# ai.net
KiCad netlist of a schematic drawn in Altium Designer
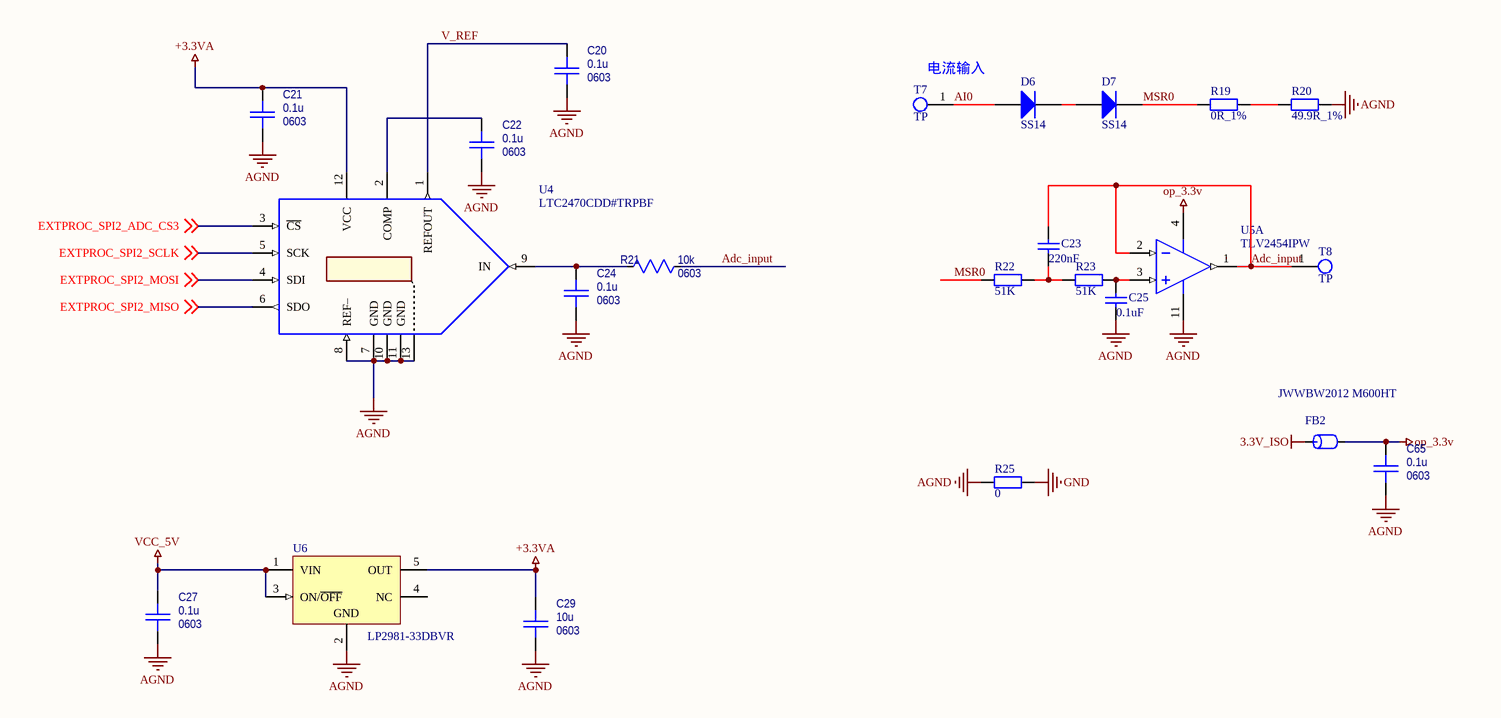
[diagram p0: ai.SchDoc]

(export (version "E")
  (design (tool "Eeschema 10.0.6"))
  (components
    (comp (ref "C20")
      (value "0.1u")
      (footprint "CAPC1608X092N_0603")
      (description "Capacitor, MLCC")
      (fields
        (field (name "PARTNUMBER") "C0603C104M5RACTU")
        (field (name "TOLERANCE") "[tol]")
        (field (name "PACKAGE") "0603")
      )
      (libsource (lib "Karl") (part "Capacitor_0603"))
    )
    (comp (ref "C21")
      (value "0.1u")
      (footprint "CAPC1608X092N_0603")
      (description "Capacitor, MLCC")
      (fields
        (field (name "PARTNUMBER") "C0603C104M5RACTU")
        (field (name "TOLERANCE") "[tol]")
        (field (name "PACKAGE") "0603")
      )
      (libsource (lib "Karl") (part "Capacitor_0603"))
    )
    (comp (ref "C22")
      (value "0.1u")
      (footprint "CAPC1608X092N_0603")
      (description "Capacitor, MLCC")
      (fields
        (field (name "PARTNUMBER") "C0603C104M5RACTU")
        (field (name "TOLERANCE") "[tol]")
        (field (name "PACKAGE") "0603")
      )
      (libsource (lib "Karl") (part "Capacitor_0603"))
    )
    (comp (ref "C23")
      (value "220nF")
      (footprint "0805C")
      (description "Capacitor")
      (fields (field (name "PUBLISHER") "Altium Limited"))
      (libsource (lib "Miscellaneous Devices") (part "Cap"))
    )
    (comp (ref "C24")
      (value "0.1u")
      (footprint "CAPC1608X092N_0603")
      (description "Capacitor, MLCC")
      (fields
        (field (name "PARTNUMBER") "C0603C104M5RACTU")
        (field (name "TOLERANCE") "[tol]")
        (field (name "PACKAGE") "0603")
      )
      (libsource (lib "Karl") (part "Capacitor_0603"))
    )
    (comp (ref "C25")
      (value "0.1uF")
      (footprint "0603C")
      (description "Capacitor")
      (fields (field (name "PUBLISHER") "Altium Limited"))
      (libsource (lib "Miscellaneous Devices") (part "Cap"))
    )
    (comp (ref "C27")
      (value "0.1u")
      (footprint "CAPC1608X092N_0603")
      (description "Capacitor, MLCC")
      (fields
        (field (name "PARTNUMBER") "C0603C104M5RACTU")
        (field (name "TOLERANCE") "[tol]")
        (field (name "PACKAGE") "0603")
      )
      (libsource (lib "Karl") (part "Capacitor_0603"))
    )
    (comp (ref "C29")
      (value "10u")
      (footprint "CAPC1608X092N_0603")
      (description "Capacitor, MLCC")
      (fields
        (field (name "PARTNUMBER") "GRM188R61A106KE69D")
        (field (name "TOLERANCE") "[tol]")
        (field (name "PACKAGE") "0603")
      )
      (libsource (lib "Karl") (part "Capacitor_0603"))
    )
    (comp (ref "C65")
      (value "0.1u")
      (footprint "CAPC1608X092N_0603")
      (description "Capacitor, MLCC")
      (fields
        (field (name "PARTNUMBER") "C0603C104M5RACTU")
        (field (name "TOLERANCE") "[tol]")
        (field (name "PACKAGE") "0603")
      )
      (libsource (lib "Karl") (part "Capacitor_0603"))
    )
    (comp (ref "D6")
      (value "SS14")
      (footprint "DO-214AC")
      (description "Default Diode")
      (fields (field (name "PUBLISHER") "Altium Limited"))
      (libsource (lib "Miscellaneous Devices") (part "Diode"))
    )
    (comp (ref "D7")
      (value "SS14")
      (footprint "DO-214AC")
      (description "Default Diode")
      (fields (field (name "PUBLISHER") "Altium Limited"))
      (libsource (lib "Miscellaneous Devices") (part "Diode"))
    )
    (comp (ref "FB2")
      (value "JWWBW2012 M600HT")
      (footprint "0805R")
      (libsource (lib "Schlib_20110825") (part "FB"))
    )
    (comp (ref "R19") (value "0R_1%") (footprint "0805R") (libsource (lib "MQlibrary") (part "Res0805M")))
    (comp (ref "R20") (value "49.9R_1%") (footprint "0805R") (libsource (lib "MQlibrary") (part "Res0805M")))
    (comp (ref "R21")
      (value "10k")
      (footprint "RESC1608X055N_0603")
      (description "Resistor, Standard")
      (fields
        (field (name "PARTNUMBER") "RR0816P-103-D")
        (field (name "TOLERANCE") "tol")
        (field (name "PACKAGE") "0603")
      )
      (libsource (lib "Karl") (part "Resistor_0603"))
    )
    (comp (ref "R22") (value "51K") (footprint "0603R") (libsource (lib "MQlibrary") (part "Res0805M")))
    (comp (ref "R23") (value "51K") (footprint "0603R") (libsource (lib "MQlibrary") (part "Res0805M")))
    (comp (ref "R25") (value "0") (footprint "1206R") (libsource (lib "MQlibrary") (part "Res0805M")))
    (comp (ref "T7") (value "TP") (footprint "TPD") (libsource (lib "Schlib_20110825") (part "TP")))
    (comp (ref "T8") (value "TP") (footprint "TPD") (libsource (lib "Schlib_20110825") (part "TP")))
    (comp (ref "U4")
      (value "LTC2470CDD#TRPBF")
      (footprint "LT-DD-12_V")
      (description "16-bit Analog-to-digital Converters, 12-pin SON (DD-12), 0 to 70 degC, Pb-Free, Tape and Reel")
      (libsource (lib "Bogen") (part "LTC2470CDD#TRPBF"))
    )
    (comp (ref "U5")
      (value "TLV2454IPW")
      (footprint "TSSOP14")
      (description "Quad High-speed, Ultra Low-power, Single-Supply TTL comparator")
      (fields (field (name "PUBLISHER") "Altium Limited"))
      (libsource (lib "Maxim Analog Comparator") (part "MAX908EPD"))
    )
    (comp (ref "U6")
      (value "LP2981-33DBVR")
      (footprint "DBV0005A_M")
      (description "Micropower 100 mA Ultra Low-Dropout Regulator, 5-pin SOT-23, Pb-Free")
      (libsource (lib "Bogen") (part "LP2981-33DBVR"))
    )
  )
  (nets
    (net (code "1") (name "+3.3VA") (class "Default")
      (node (ref "C21") (pin "1") (pinfunction "1_1") (pintype "passive"))
      (node (ref "C29") (pin "1") (pinfunction "1_1") (pintype "passive"))
      (node (ref "U4") (pin "12") (pinfunction "VCC_12") (pintype "power_in"))
      (node (ref "U6") (pin "5") (pinfunction "OUT_5") (pintype "power_in"))
    )
    (net (code "2") (name "/AI0") (class "Default")
      (node (ref "D6") (pin "1") (pinfunction "A_1") (pintype "passive"))
      (node (ref "T7") (pin "1") (pintype "passive"))
    )
    (net (code "3") (name "/Adc_input") (class "Default")
      (node (ref "C23") (pin "2") (pinfunction "2_2") (pintype "passive"))
      (node (ref "R21") (pin "1") (pinfunction "1_1") (pintype "passive"))
      (node (ref "T8") (pin "1") (pintype "passive"))
      (node (ref "U5") (pin "1") (pinfunction "OUT_1") (pintype "output"))
      (node (ref "U5") (pin "2") (pinfunction "IN-_2") (pintype "input"))
    )
    (net (code "4") (name "/MSR0") (class "Default")
      (node (ref "D7") (pin "2") (pinfunction "K_2") (pintype "passive"))
      (node (ref "R19") (pin "2") (pinfunction "2_2") (pintype "passive"))
      (node (ref "R22") (pin "2") (pinfunction "2_2") (pintype "passive"))
    )
    (net (code "5") (name "/V_REF") (class "Default")
      (node (ref "C20") (pin "1") (pinfunction "1_1") (pintype "passive"))
      (node (ref "U4") (pin "1") (pinfunction "REFOUT_1") (pintype "output"))
    )
    (net (code "6") (name "3.3V_ISO") (class "Default") (node (ref "FB2") (pin "1") (pintype "passive")))
    (net (code "7") (name "AGND") (class "Default")
      (node (ref "C20") (pin "2") (pinfunction "2_2") (pintype "passive"))
      (node (ref "C21") (pin "2") (pinfunction "2_2") (pintype "passive"))
      (node (ref "C22") (pin "2") (pinfunction "2_2") (pintype "passive"))
      (node (ref "C24") (pin "2") (pinfunction "2_2") (pintype "passive"))
      (node (ref "C25") (pin "1") (pinfunction "1_1") (pintype "passive"))
      (node (ref "C27") (pin "2") (pinfunction "2_2") (pintype "passive"))
      (node (ref "C29") (pin "2") (pinfunction "2_2") (pintype "passive"))
      (node (ref "C65") (pin "2") (pinfunction "2_2") (pintype "passive"))
      (node (ref "R20") (pin "1") (pinfunction "1_1") (pintype "passive"))
      (node (ref "R25") (pin "2") (pinfunction "2_2") (pintype "passive"))
      (node (ref "U4") (pin "10") (pinfunction "GND_10") (pintype "power_in"))
      (node (ref "U4") (pin "11") (pinfunction "GND_11") (pintype "power_in"))
      (node (ref "U4") (pin "13") (pinfunction "EP_13") (pintype "power_in"))
      (node (ref "U4") (pin "7") (pinfunction "GND_7") (pintype "power_in"))
      (node (ref "U4") (pin "8") (pinfunction "REF–_8") (pintype "input"))
      (node (ref "U5") (pin "11") (pinfunction "GND_11") (pintype "power_in"))
      (node (ref "U6") (pin "2") (pinfunction "GND_2") (pintype "power_in"))
    )
    (net (code "8") (name "EXTPROC_SPI2_ADC_CS3") (class "Default")
      (node (ref "U4") (pin "3") (pinfunction "~{CS}_3") (pintype "input"))
    )
    (net (code "9") (name "EXTPROC_SPI2_MISO") (class "Default")
      (node (ref "U4") (pin "6") (pinfunction "SDO_6") (pintype "output"))
    )
    (net (code "10") (name "EXTPROC_SPI2_MOSI") (class "Default")
      (node (ref "U4") (pin "4") (pinfunction "SDI_4") (pintype "input"))
    )
    (net (code "11") (name "EXTPROC_SPI2_SCLK") (class "Default")
      (node (ref "U4") (pin "5") (pinfunction "SCK_5") (pintype "input"))
    )
    (net (code "12") (name "GND") (class "Default")
      (node (ref "R25") (pin "1") (pinfunction "1_1") (pintype "passive"))
    )
    (net (code "13") (name "Net-(C23-Pad1)") (class "Default")
      (node (ref "C23") (pin "1") (pinfunction "1_1") (pintype "passive"))
      (node (ref "R22") (pin "1") (pinfunction "1_1") (pintype "passive"))
      (node (ref "R23") (pin "2") (pinfunction "2_2") (pintype "passive"))
    )
    (net (code "14") (name "Net-(D6-K)") (class "Default")
      (node (ref "D6") (pin "2") (pinfunction "K_2") (pintype "passive"))
      (node (ref "D7") (pin "1") (pinfunction "A_1") (pintype "passive"))
    )
    (net (code "15") (name "Net-(R19-Pad1)") (class "Default")
      (node (ref "R19") (pin "1") (pinfunction "1_1") (pintype "passive"))
      (node (ref "R20") (pin "2") (pinfunction "2_2") (pintype "passive"))
    )
    (net (code "16") (name "Net-(U4-COMP)") (class "Default")
      (node (ref "C22") (pin "1") (pinfunction "1_1") (pintype "passive"))
      (node (ref "U4") (pin "2") (pinfunction "COMP_2") (pintype "passive"))
    )
    (net (code "17") (name "Net-(U4-IN)") (class "Default")
      (node (ref "C24") (pin "1") (pinfunction "1_1") (pintype "passive"))
      (node (ref "R21") (pin "2") (pinfunction "2_2") (pintype "passive"))
      (node (ref "U4") (pin "9") (pinfunction "IN_9") (pintype "input"))
    )
    (net (code "18") (name "Net-(U5A-IN+)") (class "Default")
      (node (ref "C25") (pin "2") (pinfunction "2_2") (pintype "passive"))
      (node (ref "R23") (pin "1") (pinfunction "1_1") (pintype "passive"))
      (node (ref "U5") (pin "3") (pinfunction "IN+_3") (pintype "input"))
    )
    (net (code "19") (name "VCC_5V") (class "Default")
      (node (ref "C27") (pin "1") (pinfunction "1_1") (pintype "passive"))
      (node (ref "U6") (pin "1") (pinfunction "VIN_1") (pintype "power_in"))
      (node (ref "U6") (pin "3") (pinfunction "ON/~{OFF}_3") (pintype "input"))
    )
    (net (code "20") (name "op_3.3v") (class "Default")
      (node (ref "C65") (pin "1") (pinfunction "1_1") (pintype "passive"))
      (node (ref "FB2") (pin "2") (pintype "passive"))
      (node (ref "U5") (pin "4") (pinfunction "V+_4") (pintype "power_in"))
    )
    (net (code "21") (name "unconnected-(U6-NC-Pad4)") (class "Default")
      (node (ref "U6") (pin "4") (pinfunction "NC_4") (pintype "passive"))
    )
  )
)
